# RoomIndicator_Inside.net
KiCad netlist of a schematic drawn in EAGLE
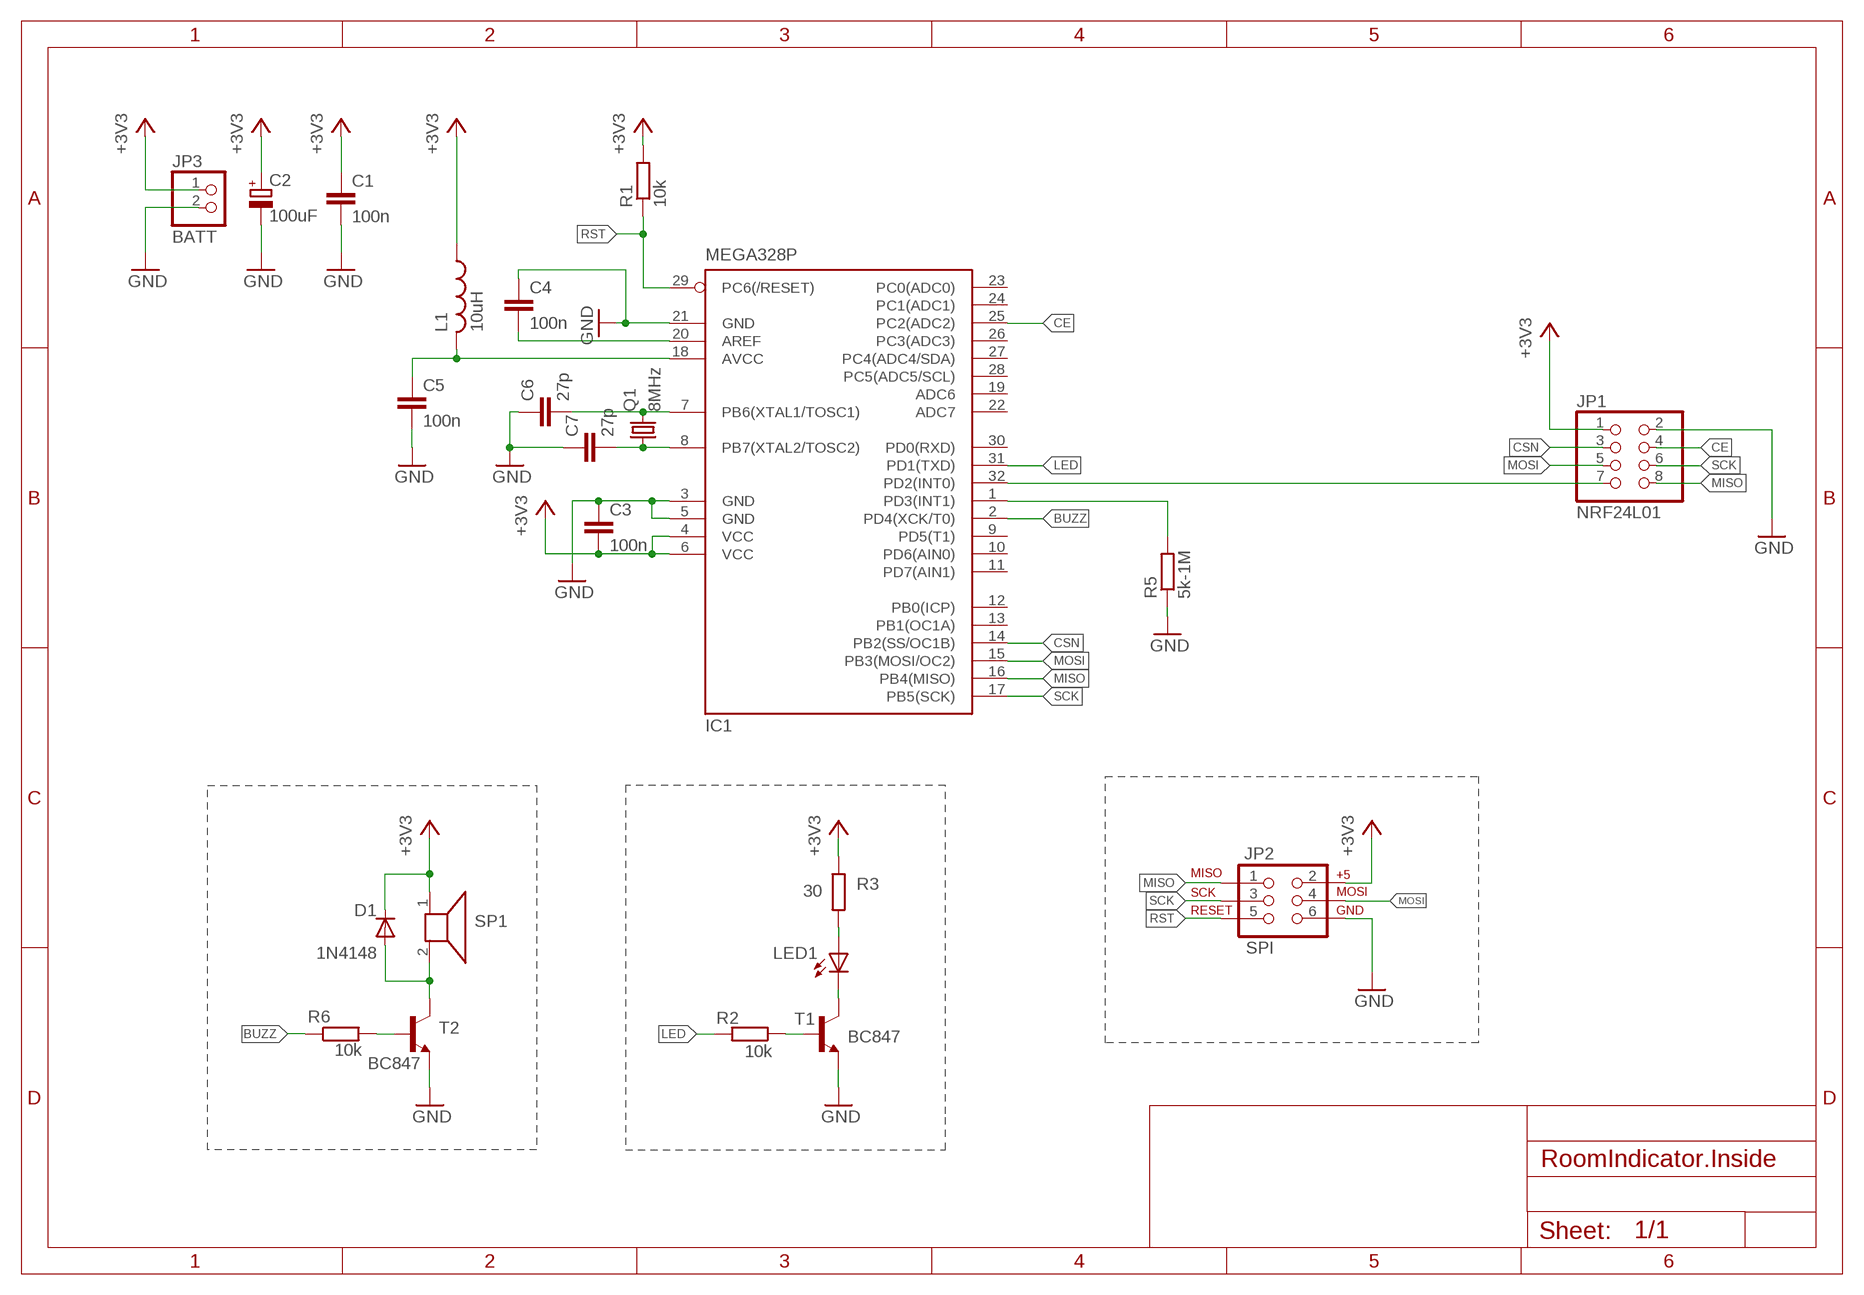
[diagram p0: schematic, sheet 1]

(export (version "E")
  (design (tool "Eeschema 10.0.6"))
  (components
    (comp (ref "C1")
      (value "100n")
      (footprint "eagle-import:C025-025X050")
      (libsource (lib "eagle-import") (part "C-EU025-025X050"))
    )
    (comp (ref "C2")
      (value "100uF")
      (footprint "eagle-import:E2,5-5")
      (libsource (lib "eagle-import") (part "CPOL-EUE2.5-5"))
    )
    (comp (ref "C3")
      (value "100n")
      (footprint "eagle-import:C0805K")
      (libsource (lib "eagle-import") (part "C-EUC0805K"))
    )
    (comp (ref "C4")
      (value "100n")
      (footprint "eagle-import:C0805K")
      (libsource (lib "eagle-import") (part "C-EUC0805K"))
    )
    (comp (ref "C5")
      (value "100n")
      (footprint "eagle-import:C0805K")
      (libsource (lib "eagle-import") (part "C-EUC0805K"))
    )
    (comp (ref "C6")
      (value "27p")
      (footprint "eagle-import:C0805K")
      (libsource (lib "eagle-import") (part "C-EUC0805K"))
    )
    (comp (ref "C7")
      (value "27p")
      (footprint "eagle-import:C0805K")
      (libsource (lib "eagle-import") (part "C-EUC0805K"))
    )
    (comp (ref "D1")
      (value "1N4148")
      (footprint "eagle-import:DO35-7")
      (libsource (lib "eagle-import") (part "1N4148DO35-7"))
    )
    (comp (ref "IC1")
      (value "MEGA328P")
      (footprint "eagle-import:TQFP32-08")
      (fields (field (name "MPN") "ATMEGA8-16AU"))
      (libsource (lib "eagle-import") (part "MEGA8-AI"))
    )
    (comp (ref "JP1")
      (value "NRF24L01")
      (footprint "eagle-import:2X04")
      (libsource (lib "eagle-import") (part "PINHD-2X4"))
    )
    (comp (ref "JP2")
      (value "SPI")
      (footprint "eagle-import:2X3")
      (libsource (lib "eagle-import") (part "AVR_SPI_PRG_6PTH"))
    )
    (comp (ref "JP3")
      (value "BATT")
      (footprint "eagle-import:1X02")
      (libsource (lib "eagle-import") (part "PINHD-1X2"))
    )
    (comp (ref "L1")
      (value "10uH")
      (footprint "eagle-import:0204_7")
      (libsource (lib "eagle-import") (part "L-US0204/7"))
    )
    (comp (ref "LED1")
      (value "GREEN")
      (footprint "eagle-import:LED5MM")
      (libsource (lib "eagle-import") (part "LED5MM"))
    )
    (comp (ref "Q1")
      (value "8MHz")
      (footprint "eagle-import:HC49_S")
      (libsource (lib "eagle-import") (part "CRYSTALHC49S"))
    )
    (comp (ref "R1")
      (value "10k")
      (footprint "eagle-import:R0805")
      (libsource (lib "eagle-import") (part "R-EU_R0805"))
    )
    (comp (ref "R2")
      (value "10k")
      (footprint "eagle-import:R0805")
      (libsource (lib "eagle-import") (part "R-EU_R0805"))
    )
    (comp (ref "R3")
      (value "30")
      (footprint "eagle-import:0204_5")
      (libsource (lib "eagle-import") (part "R-EU_0204/5"))
    )
    (comp (ref "R5")
      (value "5k-1M")
      (footprint "eagle-import:0204_5")
      (libsource (lib "eagle-import") (part "R-EU_0204/5"))
    )
    (comp (ref "R6")
      (value "10k")
      (footprint "eagle-import:R0805")
      (libsource (lib "eagle-import") (part "R-EU_R0805"))
    )
    (comp (ref "SP1")
      (value "AL60PWIDE")
      (footprint "eagle-import:AL80P")
      (libsource (lib "eagle-import") (part "AL60PWIDE"))
    )
    (comp (ref "T1")
      (value "BC847")
      (footprint "eagle-import:SOT23")
      (libsource (lib "eagle-import") (part "BC847"))
    )
    (comp (ref "T2")
      (value "BC847")
      (footprint "eagle-import:SOT23")
      (libsource (lib "eagle-import") (part "BC847"))
    )
  )
  (nets
    (net (code "1") (name "+3V3") (class "Default")
      (node (ref "C1") (pin "1") (pinfunction "1_1") (pintype "passive"))
      (node (ref "C2") (pin "+") (pinfunction "+_+") (pintype "passive"))
      (node (ref "C3") (pin "2") (pinfunction "2_2") (pintype "passive"))
      (node (ref "D1") (pin "C") (pinfunction "C_C") (pintype "passive"))
      (node (ref "IC1") (pin "4") (pinfunction "VCC_4") (pintype "power_in"))
      (node (ref "IC1") (pin "6") (pinfunction "VCC_6") (pintype "power_in"))
      (node (ref "JP1") (pin "1") (pinfunction "1_1") (pintype "passive"))
      (node (ref "JP2") (pin "2") (pinfunction "2_2") (pintype "passive"))
      (node (ref "JP3") (pin "1") (pinfunction "1_1") (pintype "passive"))
      (node (ref "L1") (pin "1") (pinfunction "1_1") (pintype "passive"))
      (node (ref "R1") (pin "2") (pinfunction "2_2") (pintype "passive"))
      (node (ref "R3") (pin "1") (pinfunction "1_1") (pintype "passive"))
      (node (ref "SP1") (pin "1") (pinfunction "1_1") (pintype "passive"))
    )
    (net (code "2") (name "BUZZ") (class "Default")
      (node (ref "IC1") (pin "2") (pinfunction "PD4(XCK/T0)_2") (pintype "bidirectional"))
      (node (ref "R6") (pin "1") (pinfunction "1_1") (pintype "passive"))
    )
    (net (code "3") (name "CE") (class "Default")
      (node (ref "IC1") (pin "25") (pinfunction "PC2(ADC2)_25") (pintype "bidirectional"))
      (node (ref "JP1") (pin "4") (pinfunction "4_4") (pintype "passive"))
    )
    (net (code "4") (name "CSN") (class "Default")
      (node (ref "IC1") (pin "14") (pinfunction "PB2(SS/OC1B)_14") (pintype "bidirectional"))
      (node (ref "JP1") (pin "3") (pinfunction "3_3") (pintype "passive"))
    )
    (net (code "5") (name "GND") (class "Default")
      (node (ref "C1") (pin "2") (pinfunction "2_2") (pintype "passive"))
      (node (ref "C2") (pin "-") (pinfunction "-_-") (pintype "passive"))
      (node (ref "C3") (pin "1") (pinfunction "1_1") (pintype "passive"))
      (node (ref "C4") (pin "1") (pinfunction "1_1") (pintype "passive"))
      (node (ref "C5") (pin "2") (pinfunction "2_2") (pintype "passive"))
      (node (ref "C6") (pin "1") (pinfunction "1_1") (pintype "passive"))
      (node (ref "C7") (pin "1") (pinfunction "1_1") (pintype "passive"))
      (node (ref "IC1") (pin "21") (pinfunction "GND_21") (pintype "power_in"))
      (node (ref "IC1") (pin "3") (pinfunction "GND_3") (pintype "power_in"))
      (node (ref "IC1") (pin "5") (pinfunction "GND_5") (pintype "power_in"))
      (node (ref "JP1") (pin "2") (pinfunction "2_2") (pintype "passive"))
      (node (ref "JP2") (pin "6") (pinfunction "6_6") (pintype "passive"))
      (node (ref "JP3") (pin "2") (pinfunction "2_2") (pintype "passive"))
      (node (ref "R5") (pin "1") (pinfunction "1_1") (pintype "passive"))
      (node (ref "T1") (pin "2") (pinfunction "E_2") (pintype "passive"))
      (node (ref "T2") (pin "2") (pinfunction "E_2") (pintype "passive"))
    )
    (net (code "6") (name "LED") (class "Default")
      (node (ref "IC1") (pin "31") (pinfunction "PD1(TXD)_31") (pintype "bidirectional"))
      (node (ref "R2") (pin "2") (pinfunction "2_2") (pintype "passive"))
    )
    (net (code "7") (name "MISO") (class "Default")
      (node (ref "IC1") (pin "16") (pinfunction "PB4(MISO)_16") (pintype "bidirectional"))
      (node (ref "JP1") (pin "8") (pinfunction "8_8") (pintype "passive"))
      (node (ref "JP2") (pin "1") (pinfunction "1_1") (pintype "passive"))
    )
    (net (code "8") (name "MOSI") (class "Default")
      (node (ref "IC1") (pin "15") (pinfunction "PB3(MOSI/OC2)_15") (pintype "bidirectional"))
      (node (ref "JP1") (pin "5") (pinfunction "5_5") (pintype "passive"))
      (node (ref "JP2") (pin "4") (pinfunction "4_4") (pintype "passive"))
    )
    (net (code "9") (name "Net-(IC1-AREF)") (class "Default")
      (node (ref "C4") (pin "2") (pinfunction "2_2") (pintype "passive"))
      (node (ref "IC1") (pin "20") (pinfunction "AREF_20") (pintype "passive"))
    )
    (net (code "10") (name "Net-(IC1-AVCC)") (class "Default")
      (node (ref "C5") (pin "1") (pinfunction "1_1") (pintype "passive"))
      (node (ref "IC1") (pin "18") (pinfunction "AVCC_18") (pintype "power_in"))
      (node (ref "L1") (pin "2") (pinfunction "2_2") (pintype "passive"))
    )
    (net (code "11") (name "Net-(IC1-PB6(XTAL1{slash}TOSC1))") (class "Default")
      (node (ref "C6") (pin "2") (pinfunction "2_2") (pintype "passive"))
      (node (ref "IC1") (pin "7") (pinfunction "PB6(XTAL1/TOSC1)_7") (pintype "bidirectional"))
      (node (ref "Q1") (pin "2") (pinfunction "2_2") (pintype "passive"))
    )
    (net (code "12") (name "Net-(IC1-PB7(XTAL2{slash}TOSC2))") (class "Default")
      (node (ref "C7") (pin "2") (pinfunction "2_2") (pintype "passive"))
      (node (ref "IC1") (pin "8") (pinfunction "PB7(XTAL2/TOSC2)_8") (pintype "bidirectional"))
      (node (ref "Q1") (pin "1") (pinfunction "1_1") (pintype "passive"))
    )
    (net (code "13") (name "Net-(IC1-PD2(INT0))") (class "Default")
      (node (ref "IC1") (pin "32") (pinfunction "PD2(INT0)_32") (pintype "bidirectional"))
      (node (ref "JP1") (pin "7") (pinfunction "7_7") (pintype "passive"))
    )
    (net (code "14") (name "Net-(IC1-PD3(INT1))") (class "Default")
      (node (ref "IC1") (pin "1") (pinfunction "PD3(INT1)_1") (pintype "bidirectional"))
      (node (ref "R5") (pin "2") (pinfunction "2_2") (pintype "passive"))
    )
    (net (code "15") (name "Net-(LED1-C)") (class "Default")
      (node (ref "LED1") (pin "K") (pinfunction "C_K") (pintype "passive"))
      (node (ref "T1") (pin "3") (pinfunction "C_3") (pintype "passive"))
    )
    (net (code "16") (name "Net-(LED1-PadA)") (class "Default")
      (node (ref "LED1") (pin "A") (pinfunction "A_A") (pintype "passive"))
      (node (ref "R3") (pin "2") (pinfunction "2_2") (pintype "passive"))
    )
    (net (code "17") (name "Net-(T1-B)") (class "Default")
      (node (ref "R2") (pin "1") (pinfunction "1_1") (pintype "passive"))
      (node (ref "T1") (pin "1") (pinfunction "B_1") (pintype "passive"))
    )
    (net (code "18") (name "Net-(T2-B)") (class "Default")
      (node (ref "R6") (pin "2") (pinfunction "2_2") (pintype "passive"))
      (node (ref "T2") (pin "1") (pinfunction "B_1") (pintype "passive"))
    )
    (net (code "19") (name "Net-(T2-C)") (class "Default")
      (node (ref "D1") (pin "A") (pinfunction "A_A") (pintype "passive"))
      (node (ref "SP1") (pin "2") (pinfunction "2_2") (pintype "passive"))
      (node (ref "T2") (pin "3") (pinfunction "C_3") (pintype "passive"))
    )
    (net (code "20") (name "RST") (class "Default")
      (node (ref "IC1") (pin "29") (pinfunction "PC6(/RESET)_29") (pintype "bidirectional"))
      (node (ref "JP2") (pin "5") (pinfunction "5_5") (pintype "passive"))
      (node (ref "R1") (pin "1") (pinfunction "1_1") (pintype "passive"))
    )
    (net (code "21") (name "SCK") (class "Default")
      (node (ref "IC1") (pin "17") (pinfunction "PB5(SCK)_17") (pintype "bidirectional"))
      (node (ref "JP1") (pin "6") (pinfunction "6_6") (pintype "passive"))
      (node (ref "JP2") (pin "3") (pinfunction "3_3") (pintype "passive"))
    )
    (net (code "22") (name "unconnected-(IC1-ADC6-Pad19)") (class "Default")
      (node (ref "IC1") (pin "19") (pinfunction "ADC6_19") (pintype "bidirectional"))
    )
    (net (code "23") (name "unconnected-(IC1-ADC7-Pad22)") (class "Default")
      (node (ref "IC1") (pin "22") (pinfunction "ADC7_22") (pintype "bidirectional"))
    )
    (net (code "24") (name "unconnected-(IC1-PB0(ICP)-Pad12)") (class "Default")
      (node (ref "IC1") (pin "12") (pinfunction "PB0(ICP)_12") (pintype "bidirectional"))
    )
    (net (code "25") (name "unconnected-(IC1-PB1(OC1A)-Pad13)") (class "Default")
      (node (ref "IC1") (pin "13") (pinfunction "PB1(OC1A)_13") (pintype "bidirectional"))
    )
    (net (code "26") (name "unconnected-(IC1-PC0(ADC0)-Pad23)") (class "Default")
      (node (ref "IC1") (pin "23") (pinfunction "PC0(ADC0)_23") (pintype "bidirectional"))
    )
    (net (code "27") (name "unconnected-(IC1-PC1(ADC1)-Pad24)") (class "Default")
      (node (ref "IC1") (pin "24") (pinfunction "PC1(ADC1)_24") (pintype "bidirectional"))
    )
    (net (code "28") (name "unconnected-(IC1-PC3(ADC3)-Pad26)") (class "Default")
      (node (ref "IC1") (pin "26") (pinfunction "PC3(ADC3)_26") (pintype "bidirectional"))
    )
    (net (code "29") (name "unconnected-(IC1-PC4(ADC4{slash}SDA)-Pad27)") (class "Default")
      (node (ref "IC1") (pin "27") (pinfunction "PC4(ADC4/SDA)_27") (pintype "bidirectional"))
    )
    (net (code "30") (name "unconnected-(IC1-PC5(ADC5{slash}SCL)-Pad28)") (class "Default")
      (node (ref "IC1") (pin "28") (pinfunction "PC5(ADC5/SCL)_28") (pintype "bidirectional"))
    )
    (net (code "31") (name "unconnected-(IC1-PD0(RXD)-Pad30)") (class "Default")
      (node (ref "IC1") (pin "30") (pinfunction "PD0(RXD)_30") (pintype "bidirectional"))
    )
    (net (code "32") (name "unconnected-(IC1-PD5(T1)-Pad9)") (class "Default")
      (node (ref "IC1") (pin "9") (pinfunction "PD5(T1)_9") (pintype "bidirectional"))
    )
    (net (code "33") (name "unconnected-(IC1-PD6(AIN0)-Pad10)") (class "Default")
      (node (ref "IC1") (pin "10") (pinfunction "PD6(AIN0)_10") (pintype "bidirectional"))
    )
    (net (code "34") (name "unconnected-(IC1-PD7(AIN1)-Pad11)") (class "Default")
      (node (ref "IC1") (pin "11") (pinfunction "PD7(AIN1)_11") (pintype "bidirectional"))
    )
  )
)
